# RJ45.net
KiCad netlist of a schematic drawn in Altium Designer
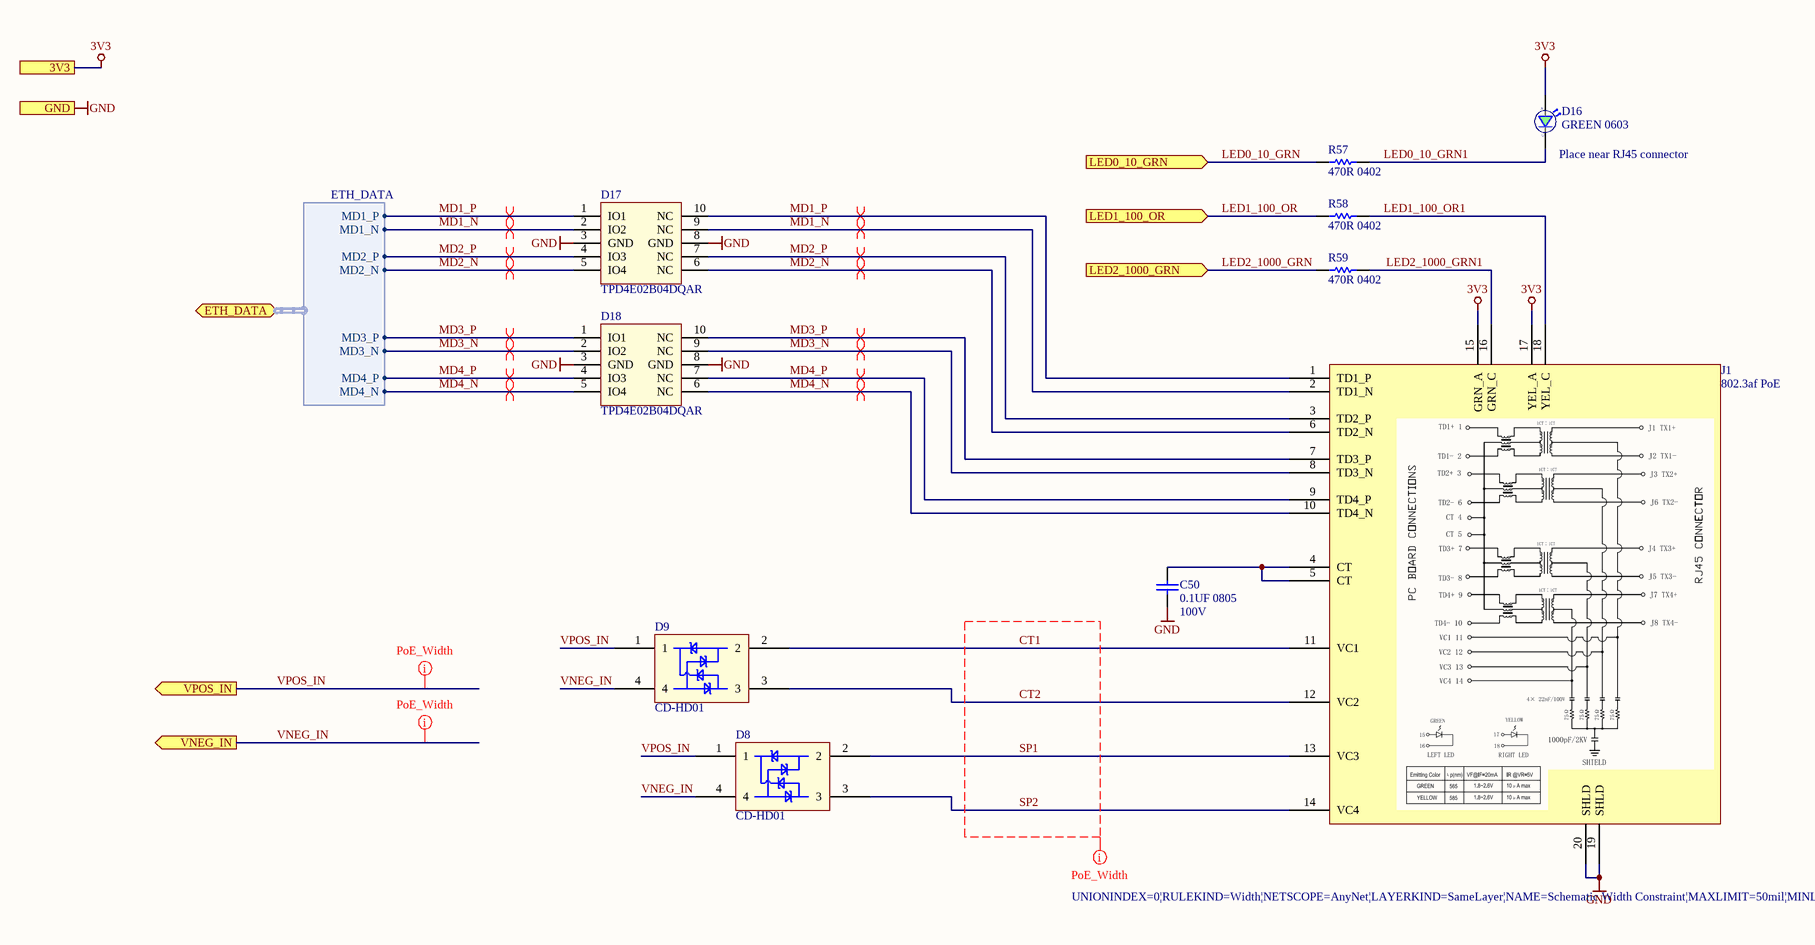
[diagram p0: RJ45.SchDoc]

(export (version "E")
  (design (tool "Eeschema 10.0.6"))
  (components
    (comp (ref "C50")
      (value "0.1UF 0805")
      (footprint "CAP_Altium_Vault_Generic:CAPC0805(2012)145_N")
      (description "CAP CER 0.1UF 100V X7R 0805")
      (fields (field (name "TOLERANCE") "10%") (field (name "VOLTAGE RATING") "100V"))
      (libsource (lib "PCBProject") (part "CL21B104KCFNNNE"))
    )
    (comp (ref "D8")
      (value "CD-HD01")
      (footprint "CD-H01")
      (description "CD-HD0x Series Schottky Bridge Rectifier Diode 100V 4-Pin Surface Mount T/R")
      (fields (field (name "MANUFACTURER") "Bourns"))
      (libsource (lib "MB2096POE") (part "CD-HD01"))
    )
    (comp (ref "D9")
      (value "CD-HD01")
      (footprint "CD-H01")
      (description "CD-HD0x Series Schottky Bridge Rectifier Diode 100V 4-Pin Surface Mount T/R")
      (fields (field (name "MANUFACTURER") "Bourns"))
      (libsource (lib "MB2096POE") (part "CD-HD01"))
    )
    (comp (ref "D16")
      (value "GREEN 0603")
      (footprint "LuxonisMaster:SML_D1xx8W")
      (description "LED GREEN DIFFUSED 0603 SMD Green 572nm LED Indication - Discrete 2.2V 0603 (1608 Metric)")
      (fields (field (name "MANUFACTURER") "Rohm") (field (name "MANUFACTURER PART NUMBER") "SML-D12M8WT86"))
      (libsource (lib "LuxonisMaster") (part "SML-D12M8WT86"))
    )
    (comp (ref "D17")
      (value "TPD4E02B04DQAR")
      (footprint "LuxonisMaster:TPD4E02B04DQAR")
      (libsource (lib "LuxonisMaster") (part "TPD4E02B04DQAR"))
    )
    (comp (ref "D18")
      (value "TPD4E02B04DQAR")
      (footprint "LuxonisMaster:TPD4E02B04DQAR")
      (libsource (lib "LuxonisMaster") (part "TPD4E02B04DQAR"))
    )
    (comp (ref "J1")
      (value "802.3af PoE")
      (footprint "BW2098POE:TRJG0926HENL")
      (description "CONN MAGJACK 1PORT 1000 BASET")
      (libsource (lib "BW2098POE") (part "TRJG0926HENL"))
    )
    (comp (ref "R57")
      (value "470R 0402")
      (footprint "RES_Altium_Vault_Generic:RESC0402(1005)_N")
      (description "RES SMD 470 OHM 1% 1/16W 0402")
      (fields (field (name "TOLERANCE") "1%"))
      (libsource (lib "LuxonisMaster") (part "CRCW0402470RFKED"))
    )
    (comp (ref "R58")
      (value "470R 0402")
      (footprint "RES_Altium_Vault_Generic:RESC0402(1005)_N")
      (description "RES SMD 470 OHM 1% 1/16W 0402")
      (fields (field (name "TOLERANCE") "1%"))
      (libsource (lib "LuxonisMaster") (part "CRCW0402470RFKED"))
    )
    (comp (ref "R59")
      (value "470R 0402")
      (footprint "RES_Altium_Vault_Generic:RESC0402(1005)_N")
      (description "RES SMD 470 OHM 1% 1/16W 0402")
      (fields (field (name "TOLERANCE") "1%"))
      (libsource (lib "LuxonisMaster") (part "CRCW0402470RFKED"))
    )
  )
  (nets
    (net (code "2") (name "/CT1") (class "Default")
      (node (ref "D9") (pin "2") (pinfunction "2_2") (pintype "passive"))
      (node (ref "J1") (pin "11") (pinfunction "VC1_11") (pintype "passive"))
    )
    (net (code "3") (name "/CT2") (class "Default")
      (node (ref "D9") (pin "3") (pinfunction "3_3") (pintype "passive"))
      (node (ref "J1") (pin "12") (pinfunction "VC2_12") (pintype "passive"))
    )
    (net (code "4") (name "/LED0_10_GRN") (class "Default")
      (node (ref "R57") (pin "1") (pinfunction "1_1") (pintype "passive"))
    )
    (net (code "5") (name "/LED0_10_GRN1") (class "Default")
      (node (ref "D16") (pin "1") (pinfunction "C_1") (pintype "passive"))
      (node (ref "R57") (pin "2") (pinfunction "2_2") (pintype "passive"))
    )
    (net (code "6") (name "/LED1_100_OR") (class "Default")
      (node (ref "R58") (pin "1") (pinfunction "1_1") (pintype "passive"))
    )
    (net (code "7") (name "/LED1_100_OR1") (class "Default")
      (node (ref "J1") (pin "18") (pinfunction "YEL_C_18") (pintype "passive"))
      (node (ref "R58") (pin "2") (pinfunction "2_2") (pintype "passive"))
    )
    (net (code "8") (name "/LED2_1000_GRN") (class "Default")
      (node (ref "R59") (pin "1") (pinfunction "1_1") (pintype "passive"))
    )
    (net (code "9") (name "/LED2_1000_GRN1") (class "Default")
      (node (ref "J1") (pin "16") (pinfunction "GRN_C_16") (pintype "passive"))
      (node (ref "R59") (pin "2") (pinfunction "2_2") (pintype "passive"))
    )
    (net (code "10") (name "/MD1_N") (class "Default")
      (node (ref "D17") (pin "2") (pinfunction "IO2_2") (pintype "passive"))
      (node (ref "D17") (pin "9") (pinfunction "NC_9") (pintype "passive"))
      (node (ref "J1") (pin "2") (pinfunction "TD1_N_2") (pintype "passive"))
    )
    (net (code "11") (name "/MD1_P") (class "Default")
      (node (ref "D17") (pin "1") (pinfunction "IO1_1") (pintype "passive"))
      (node (ref "D17") (pin "10") (pinfunction "NC_10") (pintype "passive"))
      (node (ref "J1") (pin "1") (pinfunction "TD1_P_1") (pintype "passive"))
    )
    (net (code "12") (name "/MD2_N") (class "Default")
      (node (ref "D17") (pin "5") (pinfunction "IO4_5") (pintype "passive"))
      (node (ref "D17") (pin "6") (pinfunction "NC_6") (pintype "passive"))
      (node (ref "J1") (pin "6") (pinfunction "TD2_N_6") (pintype "passive"))
    )
    (net (code "13") (name "/MD2_P") (class "Default")
      (node (ref "D17") (pin "4") (pinfunction "IO3_4") (pintype "passive"))
      (node (ref "D17") (pin "7") (pinfunction "NC_7") (pintype "passive"))
      (node (ref "J1") (pin "3") (pinfunction "TD2_P_3") (pintype "passive"))
    )
    (net (code "14") (name "/MD3_N") (class "Default")
      (node (ref "D18") (pin "2") (pinfunction "IO2_2") (pintype "passive"))
      (node (ref "D18") (pin "9") (pinfunction "NC_9") (pintype "passive"))
      (node (ref "J1") (pin "8") (pinfunction "TD3_N_8") (pintype "passive"))
    )
    (net (code "15") (name "/MD3_P") (class "Default")
      (node (ref "D18") (pin "1") (pinfunction "IO1_1") (pintype "passive"))
      (node (ref "D18") (pin "10") (pinfunction "NC_10") (pintype "passive"))
      (node (ref "J1") (pin "7") (pinfunction "TD3_P_7") (pintype "passive"))
    )
    (net (code "16") (name "/MD4_N") (class "Default")
      (node (ref "D18") (pin "5") (pinfunction "IO4_5") (pintype "passive"))
      (node (ref "D18") (pin "6") (pinfunction "NC_6") (pintype "passive"))
      (node (ref "J1") (pin "10") (pinfunction "TD4_N_10") (pintype "passive"))
    )
    (net (code "17") (name "/MD4_P") (class "Default")
      (node (ref "D18") (pin "4") (pinfunction "IO3_4") (pintype "passive"))
      (node (ref "D18") (pin "7") (pinfunction "NC_7") (pintype "passive"))
      (node (ref "J1") (pin "9") (pinfunction "TD4_P_9") (pintype "passive"))
    )
    (net (code "18") (name "/SP1") (class "Default")
      (node (ref "D8") (pin "2") (pinfunction "2_2") (pintype "passive"))
      (node (ref "J1") (pin "13") (pinfunction "VC3_13") (pintype "passive"))
    )
    (net (code "19") (name "/SP2") (class "Default")
      (node (ref "D8") (pin "3") (pinfunction "3_3") (pintype "passive"))
      (node (ref "J1") (pin "14") (pinfunction "VC4_14") (pintype "passive"))
    )
    (net (code "20") (name "/VNEG_IN") (class "Default")
      (node (ref "D8") (pin "4") (pinfunction "4_4") (pintype "passive"))
      (node (ref "D9") (pin "4") (pinfunction "4_4") (pintype "passive"))
    )
    (net (code "21") (name "/VPOS_IN") (class "Default")
      (node (ref "D8") (pin "1") (pinfunction "1_1") (pintype "passive"))
      (node (ref "D9") (pin "1") (pinfunction "1_1") (pintype "passive"))
    )
    (net (code "23") (name "3V3") (class "Default")
      (node (ref "D16") (pin "2") (pinfunction "A_2") (pintype "passive"))
      (node (ref "J1") (pin "15") (pinfunction "GRN_A_15") (pintype "passive"))
      (node (ref "J1") (pin "17") (pinfunction "YEL_A_17") (pintype "passive"))
    )
    (net (code "24") (name "GND") (class "Default")
      (node (ref "C50") (pin "1") (pinfunction "1_1") (pintype "passive"))
      (node (ref "D17") (pin "3") (pinfunction "GND_3") (pintype "passive"))
      (node (ref "D17") (pin "8") (pinfunction "GND_8") (pintype "passive"))
      (node (ref "D18") (pin "3") (pinfunction "GND_3") (pintype "passive"))
      (node (ref "D18") (pin "8") (pinfunction "GND_8") (pintype "passive"))
      (node (ref "J1") (pin "19") (pinfunction "SHLD_19") (pintype "passive"))
      (node (ref "J1") (pin "20") (pinfunction "SHLD_20") (pintype "passive"))
    )
    (net (code "25") (name "Net-(C50-Pad2)") (class "Default")
      (node (ref "C50") (pin "2") (pinfunction "2_2") (pintype "passive"))
      (node (ref "J1") (pin "4") (pinfunction "CT_4") (pintype "passive"))
      (node (ref "J1") (pin "5") (pinfunction "CT_5") (pintype "passive"))
    )
  )
)
